# JTAG.net
KiCad netlist of a schematic drawn in Altium Designer
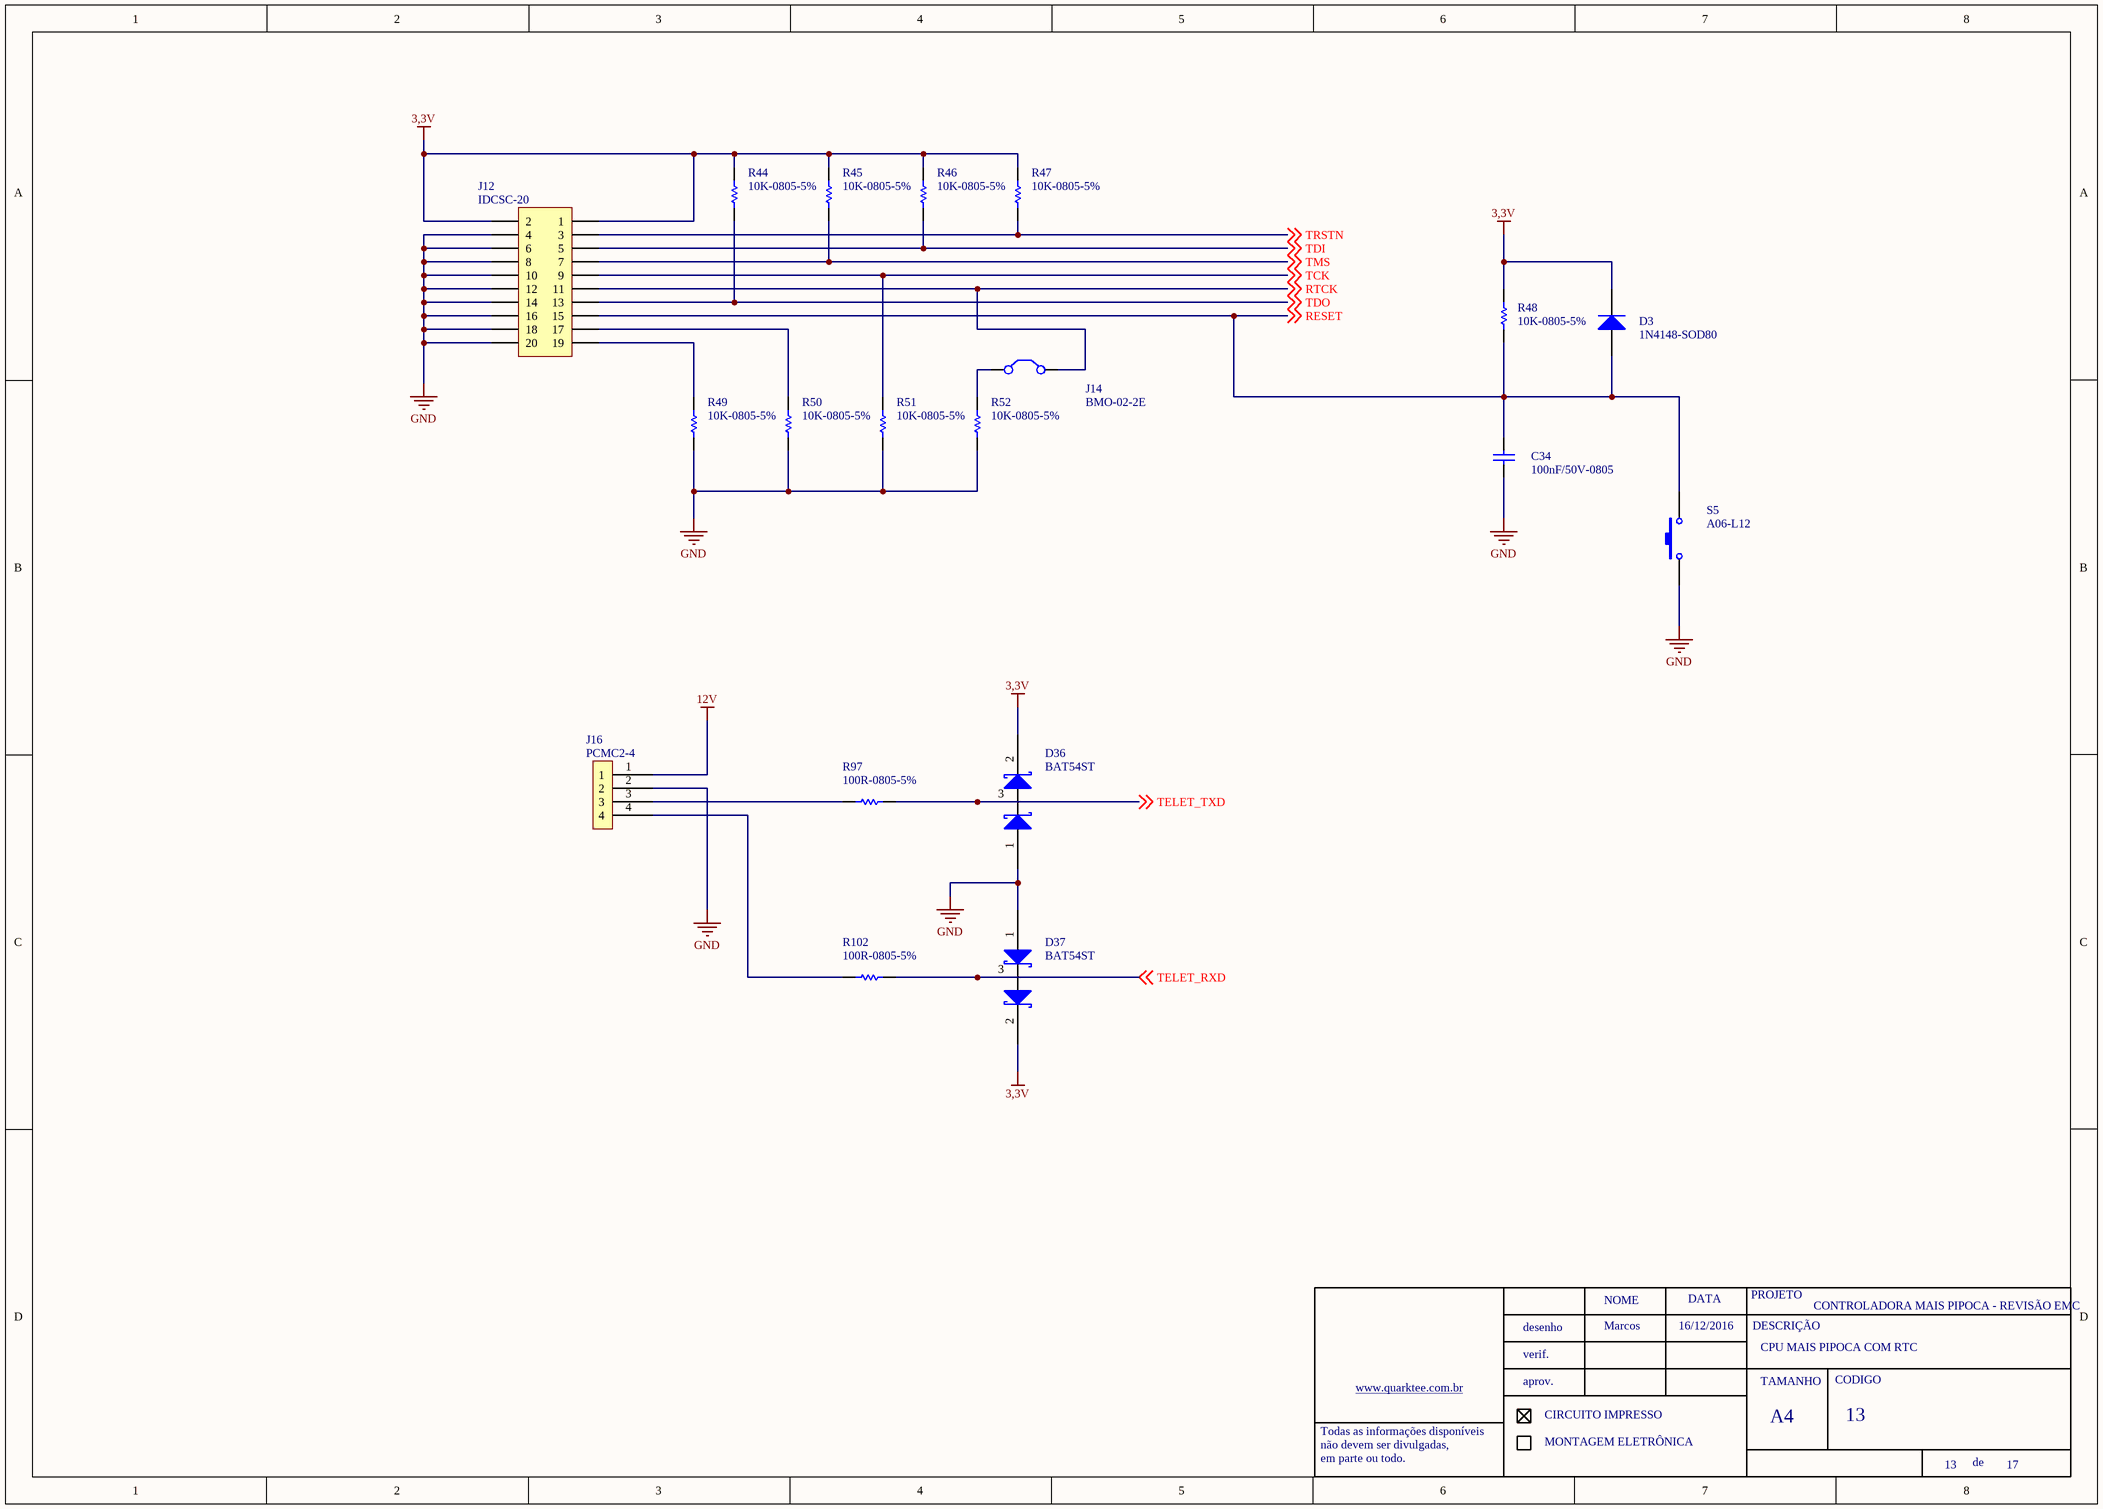
[diagram p0: JTAG.SchDoc]

(export (version "E")
  (design (tool "Eeschema 10.0.6"))
  (components
    (comp (ref "C34")
      (value "100nF/50V-0805")
      (footprint "0805-REVISADO ONDA")
      (description "100nF/50-0805-NPO")
      (libsource (lib "AquinoLib") (part "100nF/50-0805-NPO"))
    )
    (comp (ref "D3")
      (value "1N4148-SOD80")
      (footprint "MINIMLEF/SOD80 - REVISADO ONDA")
      (libsource (lib "AquinoLib") (part "1N4148-SOD80"))
    )
    (comp (ref "D36")
      (value "BAT54ST")
      (footprint "SOT23 - REVISADO ONDA")
      (libsource (lib "AquinoLib") (part "BAT54ST"))
    )
    (comp (ref "D37")
      (value "BAT54ST")
      (footprint "SOT23 - REVISADO ONDA")
      (libsource (lib "AquinoLib") (part "BAT54ST"))
    )
    (comp (ref "J12")
      (value "IDCSC-20")
      (footprint "IDCSC-20")
      (description "BARRA DE PINOS 10x2 VIAS")
      (libsource (lib "ChaveDigital") (part "HEADER 10x2"))
    )
    (comp (ref "J14")
      (value "BMO-02-2E")
      (footprint "JUMPER100")
      (libsource (lib "ChaveDigital") (part "BARRA DE PINOS"))
    )
    (comp (ref "J16") (value "PCMC2-4") (footprint "PHMC4-04") (libsource (lib "AquinoLib") (part "PCMC2-4")))
    (comp (ref "R44")
      (value "10K-0805-5%")
      (footprint "0805-REVISADO ONDA")
      (description "RES 10K-0805")
      (libsource (lib "ChaveDigital") (part "RES 10K-0805"))
    )
    (comp (ref "R45")
      (value "10K-0805-5%")
      (footprint "0805-REVISADO ONDA")
      (description "RES 10K-0805")
      (libsource (lib "ChaveDigital") (part "RES 10K-0805"))
    )
    (comp (ref "R46")
      (value "10K-0805-5%")
      (footprint "0805-REVISADO ONDA")
      (description "RES 10K-0805")
      (libsource (lib "ChaveDigital") (part "RES 10K-0805"))
    )
    (comp (ref "R47")
      (value "10K-0805-5%")
      (footprint "0805-REVISADO ONDA")
      (description "RES 10K-0805")
      (libsource (lib "ChaveDigital") (part "RES 10K-0805"))
    )
    (comp (ref "R48")
      (value "10K-0805-5%")
      (footprint "0805-REVISADO ONDA")
      (libsource (lib "AquinoLib") (part "10K-0805-5%"))
    )
    (comp (ref "R49")
      (value "10K-0805-5%")
      (footprint "0805-REVISADO ONDA")
      (description "RES 10K-0805")
      (libsource (lib "ChaveDigital") (part "RES 10K-0805"))
    )
    (comp (ref "R50")
      (value "10K-0805-5%")
      (footprint "0805-REVISADO ONDA")
      (description "RES 10K-0805")
      (libsource (lib "ChaveDigital") (part "RES 10K-0805"))
    )
    (comp (ref "R51")
      (value "10K-0805-5%")
      (footprint "0805-REVISADO ONDA")
      (description "RES 10K-0805")
      (libsource (lib "ChaveDigital") (part "RES 10K-0805"))
    )
    (comp (ref "R52")
      (value "10K-0805-5%")
      (footprint "0805-REVISADO ONDA")
      (description "RES 10K-0805")
      (libsource (lib "ChaveDigital") (part "RES 10K-0805"))
    )
    (comp (ref "R97")
      (value "100R-0805-5%")
      (footprint "0805-REVISADO ONDA")
      (libsource (lib "AquinoLib") (part "100R-0805-5%"))
    )
    (comp (ref "R102")
      (value "100R-0805-5%")
      (footprint "0805-REVISADO ONDA")
      (libsource (lib "AquinoLib") (part "100R-0805-5%"))
    )
    (comp (ref "S5")
      (value "A06-L12")
      (footprint "CHAVE_A06")
      (libsource (lib "ChaveDigital3") (part "A06-L12"))
    )
  )
  (nets
    (net (code "1") (name "3,3V") (class "Default")
      (node (ref "D3") (pin "2") (pinfunction "2_2") (pintype "passive"))
      (node (ref "D36") (pin "2") (pinfunction "2_2") (pintype "passive"))
      (node (ref "D37") (pin "2") (pinfunction "2_2") (pintype "passive"))
      (node (ref "J12") (pin "1") (pinfunction "1_1") (pintype "passive"))
      (node (ref "J12") (pin "2") (pinfunction "2_2") (pintype "passive"))
      (node (ref "R44") (pin "1") (pinfunction "1_1") (pintype "passive"))
      (node (ref "R45") (pin "1") (pinfunction "1_1") (pintype "passive"))
      (node (ref "R46") (pin "1") (pinfunction "1_1") (pintype "passive"))
      (node (ref "R47") (pin "1") (pinfunction "1_1") (pintype "passive"))
      (node (ref "R48") (pin "2") (pinfunction "2_2") (pintype "passive"))
    )
    (net (code "2") (name "12V") (class "Default")
      (node (ref "J16") (pin "1") (pinfunction "1_1") (pintype "passive"))
    )
    (net (code "3") (name "GND") (class "Default")
      (node (ref "C34") (pin "1") (pinfunction "1_1") (pintype "passive"))
      (node (ref "D36") (pin "1") (pinfunction "1_1") (pintype "passive"))
      (node (ref "D37") (pin "1") (pinfunction "1_1") (pintype "passive"))
      (node (ref "J12") (pin "10") (pinfunction "10_10") (pintype "passive"))
      (node (ref "J12") (pin "12") (pinfunction "12_12") (pintype "passive"))
      (node (ref "J12") (pin "14") (pinfunction "14_14") (pintype "passive"))
      (node (ref "J12") (pin "16") (pinfunction "16_16") (pintype "passive"))
      (node (ref "J12") (pin "18") (pinfunction "18_18") (pintype "passive"))
      (node (ref "J12") (pin "20") (pinfunction "20_20") (pintype "passive"))
      (node (ref "J12") (pin "4") (pinfunction "4_4") (pintype "passive"))
      (node (ref "J12") (pin "6") (pinfunction "6_6") (pintype "passive"))
      (node (ref "J12") (pin "8") (pinfunction "8_8") (pintype "passive"))
      (node (ref "J16") (pin "2") (pinfunction "2_2") (pintype "passive"))
      (node (ref "R49") (pin "2") (pinfunction "2_2") (pintype "passive"))
      (node (ref "R50") (pin "2") (pinfunction "2_2") (pintype "passive"))
      (node (ref "R51") (pin "2") (pinfunction "2_2") (pintype "passive"))
      (node (ref "R52") (pin "2") (pinfunction "2_2") (pintype "passive"))
      (node (ref "S5") (pin "1") (pinfunction "1_1") (pintype "passive"))
    )
    (net (code "4") (name "Net-(J12-Pad17)") (class "Default")
      (node (ref "J12") (pin "17") (pinfunction "17_17") (pintype "passive"))
      (node (ref "R50") (pin "1") (pinfunction "1_1") (pintype "passive"))
    )
    (net (code "5") (name "Net-(J12-Pad19)") (class "Default")
      (node (ref "J12") (pin "19") (pinfunction "19_19") (pintype "passive"))
      (node (ref "R49") (pin "1") (pinfunction "1_1") (pintype "passive"))
    )
    (net (code "6") (name "Net-(J14-C1)") (class "Default")
      (node (ref "J14") (pin "1") (pinfunction "C1_1") (pintype "passive"))
      (node (ref "R52") (pin "1") (pinfunction "1_1") (pintype "passive"))
    )
    (net (code "7") (name "Net-(J16-Pad3)") (class "Default")
      (node (ref "J16") (pin "3") (pinfunction "3_3") (pintype "passive"))
      (node (ref "R97") (pin "1") (pinfunction "1_1") (pintype "passive"))
    )
    (net (code "8") (name "Net-(J16-Pad4)") (class "Default")
      (node (ref "J16") (pin "4") (pinfunction "4_4") (pintype "passive"))
      (node (ref "R102") (pin "1") (pinfunction "1_1") (pintype "passive"))
    )
    (net (code "9") (name "RESET") (class "Default")
      (node (ref "C34") (pin "2") (pinfunction "2_2") (pintype "passive"))
      (node (ref "D3") (pin "1") (pinfunction "1_1") (pintype "passive"))
      (node (ref "J12") (pin "15") (pinfunction "15_15") (pintype "passive"))
      (node (ref "R48") (pin "1") (pinfunction "1_1") (pintype "passive"))
      (node (ref "S5") (pin "2") (pinfunction "2_2") (pintype "passive"))
    )
    (net (code "10") (name "RTCK") (class "Default")
      (node (ref "J12") (pin "11") (pinfunction "11_11") (pintype "passive"))
      (node (ref "J14") (pin "2") (pinfunction "C2_2") (pintype "passive"))
    )
    (net (code "11") (name "TCK") (class "Default")
      (node (ref "J12") (pin "9") (pinfunction "9_9") (pintype "passive"))
      (node (ref "R51") (pin "1") (pinfunction "1_1") (pintype "passive"))
    )
    (net (code "12") (name "TDI") (class "Default")
      (node (ref "J12") (pin "5") (pinfunction "5_5") (pintype "passive"))
      (node (ref "R46") (pin "2") (pinfunction "2_2") (pintype "passive"))
    )
    (net (code "13") (name "TDO") (class "Default")
      (node (ref "J12") (pin "13") (pinfunction "13_13") (pintype "passive"))
      (node (ref "R44") (pin "2") (pinfunction "2_2") (pintype "passive"))
    )
    (net (code "14") (name "TELET_RXD") (class "Default")
      (node (ref "D37") (pin "3") (pinfunction "3_3") (pintype "passive"))
      (node (ref "R102") (pin "2") (pinfunction "2_2") (pintype "passive"))
    )
    (net (code "15") (name "TELET_TXD") (class "Default")
      (node (ref "D36") (pin "3") (pinfunction "3_3") (pintype "passive"))
      (node (ref "R97") (pin "2") (pinfunction "2_2") (pintype "passive"))
    )
    (net (code "16") (name "TMS") (class "Default")
      (node (ref "J12") (pin "7") (pinfunction "7_7") (pintype "passive"))
      (node (ref "R45") (pin "2") (pinfunction "2_2") (pintype "passive"))
    )
    (net (code "17") (name "TRSTN") (class "Default")
      (node (ref "J12") (pin "3") (pinfunction "3_3") (pintype "passive"))
      (node (ref "R47") (pin "2") (pinfunction "2_2") (pintype "passive"))
    )
  )
)
